# oled_spi.net
KiCad netlist of a schematic drawn in EAGLE
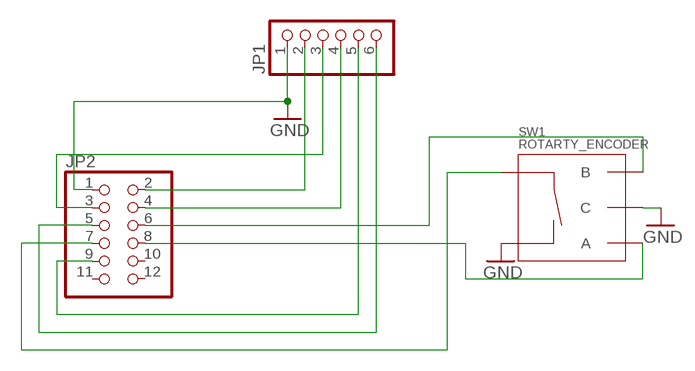
[diagram p0: schematic, sheet 1]

(export (version "E")
  (design (tool "Eeschema 10.0.6"))
  (components
    (comp (ref "JP1")
      (value "PINHD-1X6")
      (footprint "eagle-import:1X06")
      (libsource (lib "eagle-import") (part "PINHD-1X6"))
    )
    (comp (ref "JP2")
      (value "PINHD-2X6")
      (footprint "eagle-import:2X06")
      (libsource (lib "eagle-import") (part "PINHD-2X6"))
    )
    (comp (ref "SW1")
      (value "ROTARTY_ENCODER")
      (footprint "eagle-import:ROTARY_ENC_PLAIN")
      (libsource (lib "eagle-import") (part "ROTARTY_ENCODER"))
    )
  )
  (nets
    (net (code "1") (name "GND") (class "Default")
      (node (ref "JP1") (pin "1") (pinfunction "1_1") (pintype "passive"))
      (node (ref "JP2") (pin "1") (pinfunction "1_1") (pintype "passive"))
      (node (ref "SW1") (pin "C") (pinfunction "C_C") (pintype "bidirectional"))
      (node (ref "SW1") (pin "SW-") (pinfunction "SW-_SW-") (pintype "bidirectional"))
    )
    (net (code "2") (name "Net-(JP1-Pad2)") (class "Default")
      (node (ref "JP1") (pin "2") (pinfunction "2_2") (pintype "passive"))
      (node (ref "JP2") (pin "2") (pinfunction "2_2") (pintype "passive"))
    )
    (net (code "3") (name "Net-(JP1-Pad3)") (class "Default")
      (node (ref "JP1") (pin "3") (pinfunction "3_3") (pintype "passive"))
      (node (ref "JP2") (pin "3") (pinfunction "3_3") (pintype "passive"))
    )
    (net (code "4") (name "Net-(JP1-Pad4)") (class "Default")
      (node (ref "JP1") (pin "4") (pinfunction "4_4") (pintype "passive"))
      (node (ref "JP2") (pin "4") (pinfunction "4_4") (pintype "passive"))
    )
    (net (code "5") (name "Net-(JP1-Pad5)") (class "Default")
      (node (ref "JP1") (pin "5") (pinfunction "5_5") (pintype "passive"))
      (node (ref "JP2") (pin "9") (pinfunction "9_9") (pintype "passive"))
    )
    (net (code "6") (name "Net-(JP1-Pad6)") (class "Default")
      (node (ref "JP1") (pin "6") (pinfunction "6_6") (pintype "passive"))
      (node (ref "JP2") (pin "5") (pinfunction "5_5") (pintype "passive"))
    )
    (net (code "7") (name "Net-(JP2-Pad6)") (class "Default")
      (node (ref "JP2") (pin "6") (pinfunction "6_6") (pintype "passive"))
      (node (ref "SW1") (pin "B") (pinfunction "B_B") (pintype "bidirectional"))
    )
    (net (code "8") (name "Net-(JP2-Pad7)") (class "Default")
      (node (ref "JP2") (pin "7") (pinfunction "7_7") (pintype "passive"))
      (node (ref "SW1") (pin "SW+") (pinfunction "SW+_SW+") (pintype "bidirectional"))
    )
    (net (code "9") (name "Net-(JP2-Pad8)") (class "Default")
      (node (ref "JP2") (pin "8") (pinfunction "8_8") (pintype "passive"))
      (node (ref "SW1") (pin "A") (pinfunction "A_A") (pintype "bidirectional"))
    )
    (net (code "10") (name "unconnected-(JP2-Pad10)") (class "Default")
      (node (ref "JP2") (pin "10") (pinfunction "10_10") (pintype "passive"))
    )
    (net (code "11") (name "unconnected-(JP2-Pad11)") (class "Default")
      (node (ref "JP2") (pin "11") (pinfunction "11_11") (pintype "passive"))
    )
    (net (code "12") (name "unconnected-(JP2-Pad12)") (class "Default")
      (node (ref "JP2") (pin "12") (pinfunction "12_12") (pintype "passive"))
    )
  )
)
